# MPL_Breakout.net
KiCad netlist of a schematic drawn in EAGLE
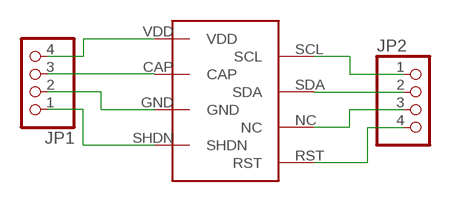
[diagram p0: schematic, sheet 1]

(export (version "E")
  (design (tool "Eeschema 10.0.6"))
  (components
    (comp (ref "B1")
      (value "MPL115A2T1")
      (footprint "eagle-import:MPL115A2T1")
      (libsource (lib "eagle-import") (part "MPL115A2T1"))
    )
    (comp (ref "JP1")
      (value "PINHD-1X4")
      (footprint "eagle-import:1X04")
      (libsource (lib "eagle-import") (part "PINHD-1X4"))
    )
    (comp (ref "JP2")
      (value "PINHD-1X4")
      (footprint "eagle-import:1X04")
      (libsource (lib "eagle-import") (part "PINHD-1X4"))
    )
  )
  (nets
    (net (code "1") (name "Net-(B1-PadCAP)") (class "Default")
      (node (ref "B1") (pin "CAP") (pinfunction "CAP_CAP") (pintype "bidirectional"))
      (node (ref "JP1") (pin "3") (pinfunction "3_3") (pintype "passive"))
    )
    (net (code "2") (name "Net-(B1-PadGND)") (class "Default")
      (node (ref "B1") (pin "GND") (pinfunction "GND_GND") (pintype "bidirectional"))
      (node (ref "JP1") (pin "2") (pinfunction "2_2") (pintype "passive"))
    )
    (net (code "3") (name "Net-(B1-PadNC)") (class "Default")
      (node (ref "B1") (pin "NC") (pinfunction "NC_NC") (pintype "bidirectional"))
      (node (ref "JP2") (pin "3") (pinfunction "3_3") (pintype "passive"))
    )
    (net (code "4") (name "Net-(B1-PadRST)") (class "Default")
      (node (ref "B1") (pin "RST") (pinfunction "RST_RST") (pintype "bidirectional"))
      (node (ref "JP2") (pin "4") (pinfunction "4_4") (pintype "passive"))
    )
    (net (code "5") (name "Net-(B1-PadSCL)") (class "Default")
      (node (ref "B1") (pin "SCL") (pinfunction "SCL_SCL") (pintype "bidirectional"))
      (node (ref "JP2") (pin "1") (pinfunction "1_1") (pintype "passive"))
    )
    (net (code "6") (name "Net-(B1-PadSDA)") (class "Default")
      (node (ref "B1") (pin "SDA") (pinfunction "SDA_SDA") (pintype "bidirectional"))
      (node (ref "JP2") (pin "2") (pinfunction "2_2") (pintype "passive"))
    )
    (net (code "7") (name "Net-(B1-PadSHDN)") (class "Default")
      (node (ref "B1") (pin "SHDN") (pinfunction "SHDN_SHDN") (pintype "bidirectional"))
      (node (ref "JP1") (pin "1") (pinfunction "1_1") (pintype "passive"))
    )
    (net (code "8") (name "Net-(B1-PadVDD)") (class "Default")
      (node (ref "B1") (pin "VDD") (pinfunction "VDD_VDD") (pintype "bidirectional"))
      (node (ref "JP1") (pin "4") (pinfunction "4_4") (pintype "passive"))
    )
  )
)
